# NEW_7V_Buck_LDO_Power.net
KiCad netlist of a schematic drawn in Altium Designer
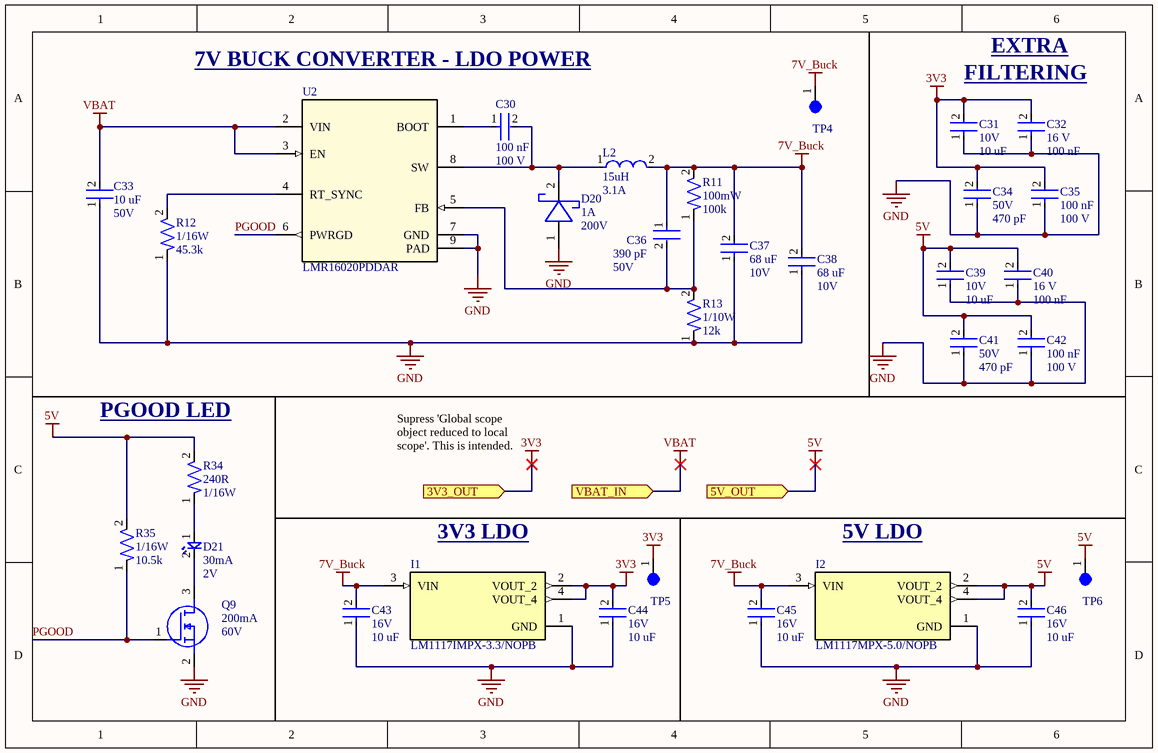
[diagram p0: NEW_7V_Buck_LDO_Power.SchDoc]

(export (version "E")
  (design (tool "Eeschema 10.0.6"))
  (components
    (comp (ref "C30")
      (value "CC0603KRX7R0BB104")
      (footprint "CAP-0603")
      (description "CAP CER 0.1UF 100V X7R 0603")
      (fields (field (name "CAPACITANCE") "100 nF") (field (name "VOLTAGE") "100 V"))
      (libsource (lib "JLC_25") (part "CAP-100N-0001"))
    )
    (comp (ref "C31")
      (value "CC0603KRX5R6BB106")
      (footprint "CAP-0603")
      (description "CAP CER 10UF 10V X5R 0603")
      (fields (field (name "VOLTAGE") "10V") (field (name "CAPACITANCE") "10 uF"))
      (libsource (lib "JLC_25") (part "CAP-10U-0001"))
    )
    (comp (ref "C32")
      (value "CC0402KRX7R7BB104")
      (footprint "CAP-0402")
      (description "CAP CER 0.1UF 16V X7R 0402")
      (fields (field (name "VOLTAGE RATING") "16 V") (field (name "CAPACITANCE") "100 nF"))
      (libsource (lib "JLC_25") (part "CAP-0.1U-0001"))
    )
    (comp (ref "C33")
      (value "CL32B106KBJNNNE")
      (footprint "CAP-1210")
      (description "CAP CER 10UF 50V X7R 1210")
      (fields (field (name "VOLTAGE") "50V") (field (name "CAPACITANCE") "10 uF"))
      (libsource (lib "JLC_25") (part "CAP-10U-0002"))
    )
    (comp (ref "C34")
      (value "CC0805JRNPO9BN471")
      (footprint "CAP-0805")
      (description "CAP CER 470PF 50V C0G/NPO 0805")
      (fields (field (name "VOLTAGE") "50V") (field (name "CAPACITANCE") "470 pF"))
      (libsource (lib "JLC_25") (part "CAP-470P-0001"))
    )
    (comp (ref "C35")
      (value "CC0603KRX7R0BB104")
      (footprint "CAP-0603")
      (description "CAP CER 0.1UF 100V X7R 0603")
      (fields (field (name "CAPACITANCE") "100 nF") (field (name "VOLTAGE") "100 V"))
      (libsource (lib "JLC_25") (part "CAP-100N-0001"))
    )
    (comp (ref "C36")
      (value "GRM155R71H391KA01D")
      (footprint "CAP-0402")
      (description "CAP CER 390PF 50V X7R 0402")
      (fields (field (name "CAPACITANCE") "390 pF") (field (name "VOLTAGE") "50V"))
      (libsource (lib "JLC_25") (part "CAP-390P-0001_1"))
    )
    (comp (ref "C37")
      (value "C5750X5R1A686MT000N")
      (footprint "CAP-1210")
      (description "CAP CER 68UF 10V X5R 2220")
      (fields (field (name "CAPACITANCE") "68 uF") (field (name "VOLTAGE") "10V"))
      (libsource (lib "JLC_25") (part "CAP-68U-0001"))
    )
    (comp (ref "C38")
      (value "C5750X5R1A686MT000N")
      (footprint "CAP-1210")
      (description "CAP CER 68UF 10V X5R 2220")
      (fields (field (name "CAPACITANCE") "68 uF") (field (name "VOLTAGE") "10V"))
      (libsource (lib "JLC_25") (part "CAP-68U-0001"))
    )
    (comp (ref "C39")
      (value "CC0603KRX5R6BB106")
      (footprint "CAP-0603")
      (description "CAP CER 10UF 10V X5R 0603")
      (fields (field (name "VOLTAGE") "10V") (field (name "CAPACITANCE") "10 uF"))
      (libsource (lib "JLC_25") (part "CAP-10U-0001"))
    )
    (comp (ref "C40")
      (value "CC0402KRX7R7BB104")
      (footprint "CAP-0402")
      (description "CAP CER 0.1UF 16V X7R 0402")
      (fields (field (name "VOLTAGE RATING") "16 V") (field (name "CAPACITANCE") "100 nF"))
      (libsource (lib "JLC_25") (part "CAP-0.1U-0001"))
    )
    (comp (ref "C41")
      (value "CC0805JRNPO9BN471")
      (footprint "CAP-0805")
      (description "CAP CER 470PF 50V C0G/NPO 0805")
      (fields (field (name "VOLTAGE") "50V") (field (name "CAPACITANCE") "470 pF"))
      (libsource (lib "JLC_25") (part "CAP-470P-0001"))
    )
    (comp (ref "C42")
      (value "CC0603KRX7R0BB104")
      (footprint "CAP-0603")
      (description "CAP CER 0.1UF 100V X7R 0603")
      (fields (field (name "CAPACITANCE") "100 nF") (field (name "VOLTAGE") "100 V"))
      (libsource (lib "JLC_25") (part "CAP-100N-0001"))
    )
    (comp (ref "C43")
      (value "293D106X9016A2TE3")
      (footprint "CAP-1210")
      (description "CAP TANT 10UF 10% 16V 1206")
      (fields (field (name "VOLTAGE") "16V") (field (name "CAPACITANCE") "10 uF"))
      (libsource (lib "JLC_25") (part "CAP-10U-0003"))
    )
    (comp (ref "C44")
      (value "293D106X9016A2TE3")
      (footprint "CAP-1210")
      (description "CAP TANT 10UF 10% 16V 1206")
      (fields (field (name "VOLTAGE") "16V") (field (name "CAPACITANCE") "10 uF"))
      (libsource (lib "JLC_25") (part "CAP-10U-0003"))
    )
    (comp (ref "C45")
      (value "293D106X9016A2TE3")
      (footprint "CAP-1210")
      (description "CAP TANT 10UF 10% 16V 1206")
      (fields (field (name "VOLTAGE") "16V") (field (name "CAPACITANCE") "10 uF"))
      (libsource (lib "JLC_25") (part "CAP-10U-0003"))
    )
    (comp (ref "C46")
      (value "293D106X9016A2TE3")
      (footprint "CAP-1210")
      (description "CAP TANT 10UF 10% 16V 1206")
      (fields (field (name "VOLTAGE") "16V") (field (name "CAPACITANCE") "10 uF"))
      (libsource (lib "JLC_25") (part "CAP-10U-0003"))
    )
    (comp (ref "D20")
      (value "SS1200")
      (footprint "SMA_DIO")
      (description "DIODE SCHOTTKY 200V 1A SMA")
      (fields (field (name "CURRENT RATING") "1A") (field (name "REVERSE VOLTAGE") "200V"))
      (libsource (lib "JLC_25") (part "DIO-SCHOTTKY-0004"))
    )
    (comp (ref "D21")
      (value "BL-HKC36G-AV-TRB")
      (footprint "LED-0603")
      (description "LED YELLOW CLEAR 0603 SMD")
      (fields (field (name "FORWARD CURRENT") "30mA") (field (name "FORWARD VOLTAGE") "2V"))
      (libsource (lib "JLC_25") (part "LED-0001"))
    )
    (comp (ref "I1")
      (value "LM1117IMPX-3.3/NOPB")
      (footprint "IC-SOT-223-4")
      (description "IC REG LIN 3.3V 800MA SOT223-4")
      (libsource (lib "JLC_25") (part "IC_LDO_3V3_0001"))
    )
    (comp (ref "I2")
      (value "LM1117MPX-5.0/NOPB")
      (footprint "IC-SOT-223-4")
      (description "IC REG LINEAR 5V 800MA SOT223-4")
      (libsource (lib "JLC_25") (part "IC_LDO_5V_0001"))
    )
    (comp (ref "L2")
      (value "CSAD1010-150M")
      (footprint "IND-15UH-0001")
      (description "FIXED IND 15UH 3.1A 50 MOHM SMD")
      (fields (field (name "INDUCTANCE") "15uH") (field (name "CURRENT RATING") "3.1A"))
      (libsource (lib "JLC_25") (part "IND-15U-0001-NoJLC"))
    )
    (comp (ref "Q9")
      (value "T2N7002AK,LM")
      (footprint "IC-SOT23-3")
      (description "MOSFET N-CH 60V 200MA SOT23")
      (fields (field (name "CONTINUOUS CURRENT") "200mA") (field (name "VOLTAGE") "60V"))
      (libsource (lib "JLC_25") (part "NMOS-200MA-0001"))
    )
    (comp (ref "R11")
      (value "RC0603FR-07100KL")
      (footprint "RES-0603")
      (description "RES SMD 100K OHM 1% 1/10W 0603")
      (fields
        (field (name "TOLERANCE") "1%")
        (field (name "POWER") "100mW")
        (field (name "RESISTANCE") "100k")
      )
      (libsource (lib "JLC_25") (part "RES-100k-0001"))
    )
    (comp (ref "R12")
      (value "RC0402FR-0745K3L")
      (footprint "RES-0402")
      (description "RES 45.3K OHM 1% 1/16W 0402")
      (fields
        (field (name "TOLERANCE") "1%")
        (field (name "POWER") "1/16W")
        (field (name "RESISTANCE") "45.3k")
      )
      (libsource (lib "JLC_25") (part "RES-43.5k-0001"))
    )
    (comp (ref "R13")
      (value "RC0603FR-0712KL")
      (footprint "RES-0603")
      (description "RES 12K OHM 1% 1/10W 0603")
      (fields
        (field (name "TOLERANCE") "1%")
        (field (name "POWER") "1/10W")
        (field (name "RESISTANCE") "12k")
      )
      (libsource (lib "JLC_25") (part "RES-12k-0001"))
    )
    (comp (ref "R34")
      (value "RC0402FR-07240RL")
      (footprint "RES-0402")
      (description "240R 0.063W 1% 0402 (1005 Metric)  SMD")
      (fields
        (field (name "TOLERANCE") "1%")
        (field (name "RESISTANCE") "240R")
        (field (name "POWER") "1/16W")
      )
      (libsource (lib "JLC_25") (part "RES-240-0001"))
    )
    (comp (ref "R35")
      (value "RC0402FR-0710K5L")
      (footprint "RES-0402")
      (description "RES 10.5K OHM 1% 1/16W 0402")
      (fields
        (field (name "TOLERANCE") "1%")
        (field (name "POWER") "1/16W")
        (field (name "RESISTANCE") "10.5k")
      )
      (libsource (lib "JLC_25") (part "RES-10.5k-0001"))
    )
    (comp (ref "TP4")
      (value "5003")
      (footprint "TEST-POINT-0001")
      (description "Oranange PC Test Point, Miniature Phoisphor Bronze Silver Plating Through Hole Mounting Type")
      (libsource (lib "*") (part "TEST-POINT-0001"))
    )
    (comp (ref "TP5")
      (value "5003")
      (footprint "TEST-POINT-0001")
      (description "Oranange PC Test Point, Miniature Phoisphor Bronze Silver Plating Through Hole Mounting Type")
      (libsource (lib "*") (part "TEST-POINT-0001"))
    )
    (comp (ref "TP6")
      (value "5003")
      (footprint "TEST-POINT-0001")
      (description "Oranange PC Test Point, Miniature Phoisphor Bronze Silver Plating Through Hole Mounting Type")
      (libsource (lib "*") (part "TEST-POINT-0001"))
    )
    (comp (ref "U2")
      (value "LMR16020PDDAR")
      (footprint "IC-8SOPWR")
      (description "IC REG BUCK ADJ 2A 8SOPWR")
      (libsource (lib "JLC_25") (part "IC_BUCK_7V_0001"))
    )
  )
  (nets
    (net (code "1") (name "/PGOOD") (class "Default")
      (node (ref "Q9") (pin "1") (pinfunction "G_1") (pintype "passive"))
      (node (ref "R35") (pin "1") (pinfunction "1_1") (pintype "passive"))
      (node (ref "U2") (pin "6") (pinfunction "PWRGD_6") (pintype "output"))
    )
    (net (code "2") (name "3V3") (class "Default")
      (node (ref "C31") (pin "2") (pinfunction "2_2") (pintype "passive"))
      (node (ref "C32") (pin "2") (pinfunction "2_2") (pintype "passive"))
      (node (ref "C34") (pin "2") (pinfunction "2_2") (pintype "passive"))
      (node (ref "C35") (pin "2") (pinfunction "2_2") (pintype "passive"))
      (node (ref "C44") (pin "2") (pinfunction "2_2") (pintype "passive"))
      (node (ref "I1") (pin "2") (pinfunction "VOUT_2_2") (pintype "output"))
      (node (ref "I1") (pin "4") (pinfunction "VOUT_4_4") (pintype "output"))
      (node (ref "TP5") (pin "1") (pinfunction "0_1") (pintype "passive"))
    )
    (net (code "3") (name "5V") (class "Default")
      (node (ref "C39") (pin "2") (pinfunction "2_2") (pintype "passive"))
      (node (ref "C40") (pin "2") (pinfunction "2_2") (pintype "passive"))
      (node (ref "C41") (pin "2") (pinfunction "2_2") (pintype "passive"))
      (node (ref "C42") (pin "2") (pinfunction "2_2") (pintype "passive"))
      (node (ref "C46") (pin "2") (pinfunction "2_2") (pintype "passive"))
      (node (ref "I2") (pin "2") (pinfunction "VOUT_2_2") (pintype "output"))
      (node (ref "I2") (pin "4") (pinfunction "VOUT_4_4") (pintype "output"))
      (node (ref "R34") (pin "2") (pinfunction "2_2") (pintype "passive"))
      (node (ref "R35") (pin "2") (pinfunction "2_2") (pintype "passive"))
      (node (ref "TP6") (pin "1") (pinfunction "0_1") (pintype "passive"))
    )
    (net (code "4") (name "7V_Buck") (class "Default")
      (node (ref "C36") (pin "1") (pinfunction "1_1") (pintype "passive"))
      (node (ref "C37") (pin "2") (pinfunction "2_2") (pintype "passive"))
      (node (ref "C38") (pin "2") (pinfunction "2_2") (pintype "passive"))
      (node (ref "C43") (pin "2") (pinfunction "2_2") (pintype "passive"))
      (node (ref "C45") (pin "2") (pinfunction "2_2") (pintype "passive"))
      (node (ref "I1") (pin "3") (pinfunction "VIN_3") (pintype "input"))
      (node (ref "I2") (pin "3") (pinfunction "VIN_3") (pintype "input"))
      (node (ref "L2") (pin "2") (pinfunction "2_2") (pintype "passive"))
      (node (ref "R11") (pin "2") (pinfunction "2_2") (pintype "passive"))
      (node (ref "TP4") (pin "1") (pinfunction "0_1") (pintype "passive"))
    )
    (net (code "5") (name "GND") (class "Default")
      (node (ref "C31") (pin "1") (pinfunction "1_1") (pintype "passive"))
      (node (ref "C32") (pin "1") (pinfunction "1_1") (pintype "passive"))
      (node (ref "C33") (pin "1") (pinfunction "1_1") (pintype "passive"))
      (node (ref "C34") (pin "1") (pinfunction "1_1") (pintype "passive"))
      (node (ref "C35") (pin "1") (pinfunction "1_1") (pintype "passive"))
      (node (ref "C37") (pin "1") (pinfunction "1_1") (pintype "passive"))
      (node (ref "C38") (pin "1") (pinfunction "1_1") (pintype "passive"))
      (node (ref "C39") (pin "1") (pinfunction "1_1") (pintype "passive"))
      (node (ref "C40") (pin "1") (pinfunction "1_1") (pintype "passive"))
      (node (ref "C41") (pin "1") (pinfunction "1_1") (pintype "passive"))
      (node (ref "C42") (pin "1") (pinfunction "1_1") (pintype "passive"))
      (node (ref "C43") (pin "1") (pinfunction "1_1") (pintype "passive"))
      (node (ref "C44") (pin "1") (pinfunction "1_1") (pintype "passive"))
      (node (ref "C45") (pin "1") (pinfunction "1_1") (pintype "passive"))
      (node (ref "C46") (pin "1") (pinfunction "1_1") (pintype "passive"))
      (node (ref "D20") (pin "1") (pinfunction "CATHODE_1") (pintype "passive"))
      (node (ref "I1") (pin "1") (pinfunction "GND_1") (pintype "power_in"))
      (node (ref "I2") (pin "1") (pinfunction "GND_1") (pintype "power_in"))
      (node (ref "Q9") (pin "2") (pinfunction "S_2") (pintype "passive"))
      (node (ref "R12") (pin "1") (pinfunction "1_1") (pintype "passive"))
      (node (ref "R13") (pin "1") (pinfunction "1_1") (pintype "passive"))
      (node (ref "U2") (pin "7") (pinfunction "GND_7") (pintype "power_in"))
      (node (ref "U2") (pin "9") (pinfunction "PAD_9") (pintype "power_in"))
    )
    (net (code "6") (name "Net-(D20-ANODE)") (class "Default")
      (node (ref "C30") (pin "2") (pinfunction "2_2") (pintype "passive"))
      (node (ref "D20") (pin "2") (pinfunction "ANODE_2") (pintype "passive"))
      (node (ref "L2") (pin "1") (pinfunction "1_1") (pintype "passive"))
      (node (ref "U2") (pin "8") (pinfunction "SW_8") (pintype "power_in"))
    )
    (net (code "7") (name "Net-(D21-Pad1)") (class "Default")
      (node (ref "D21") (pin "1") (pinfunction "1_1") (pintype "passive"))
      (node (ref "R34") (pin "1") (pinfunction "1_1") (pintype "passive"))
    )
    (net (code "8") (name "Net-(Q9-D)") (class "Default")
      (node (ref "D21") (pin "2") (pinfunction "2_2") (pintype "passive"))
      (node (ref "Q9") (pin "3") (pinfunction "D_3") (pintype "passive"))
    )
    (net (code "9") (name "Net-(U2-BOOT)") (class "Default")
      (node (ref "C30") (pin "1") (pinfunction "1_1") (pintype "passive"))
      (node (ref "U2") (pin "1") (pinfunction "BOOT_1") (pintype "passive"))
    )
    (net (code "10") (name "Net-(U2-FB)") (class "Default")
      (node (ref "C36") (pin "2") (pinfunction "2_2") (pintype "passive"))
      (node (ref "R11") (pin "1") (pinfunction "1_1") (pintype "passive"))
      (node (ref "R13") (pin "2") (pinfunction "2_2") (pintype "passive"))
      (node (ref "U2") (pin "5") (pinfunction "FB_5") (pintype "input"))
    )
    (net (code "11") (name "Net-(U2-RT_SYNC)") (class "Default")
      (node (ref "R12") (pin "2") (pinfunction "2_2") (pintype "passive"))
      (node (ref "U2") (pin "4") (pinfunction "RT_SYNC_4") (pintype "passive"))
    )
    (net (code "12") (name "VBAT") (class "Default")
      (node (ref "C33") (pin "2") (pinfunction "2_2") (pintype "passive"))
      (node (ref "U2") (pin "2") (pinfunction "VIN_2") (pintype "power_in"))
      (node (ref "U2") (pin "3") (pinfunction "EN_3") (pintype "input"))
    )
  )
)
